# 140810_AriloTX_REV3_0_0_868MHZ_td.net
KiCad netlist of a schematic drawn in EAGLE
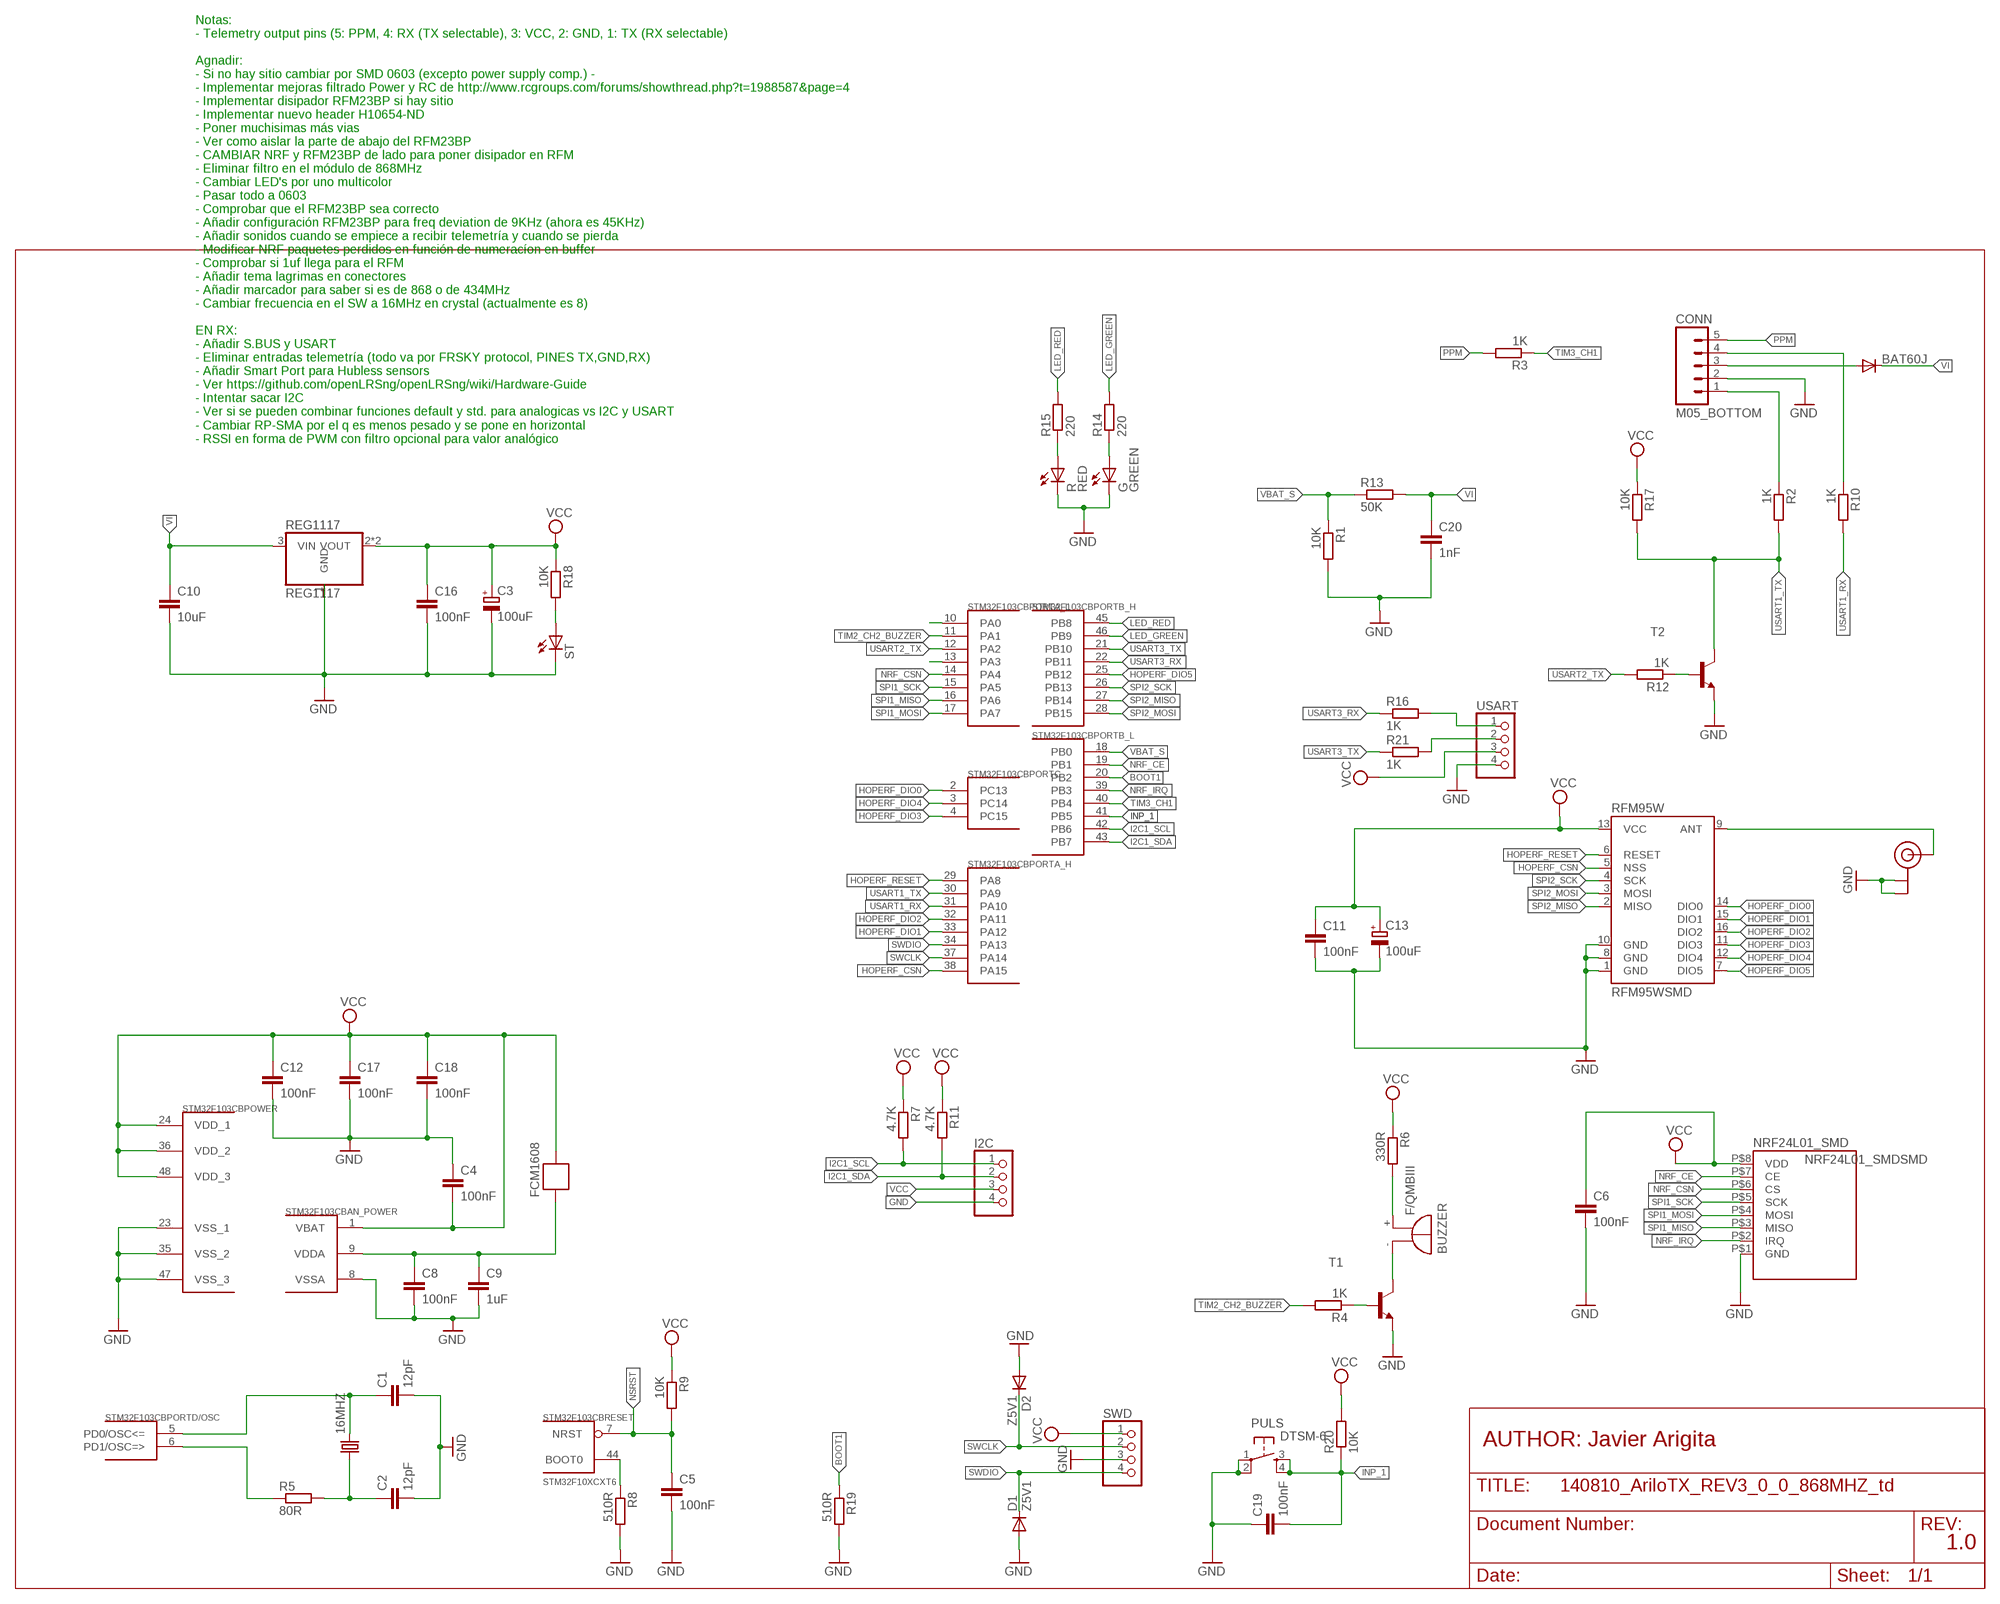
[diagram p0: schematic, sheet 1]

(export (version "E")
  (design (tool "Eeschema 10.0.6"))
  (components
    (comp (ref "16MHZ")
      (value "CRYSTAL5X3")
      (footprint "eagle-import:CRYSTAL-SMD-5X3")
      (libsource (lib "eagle-import") (part "CRYSTAL5X3"))
    )
    (comp (ref "BAT60J")
      (value "DIODE-SOD323-R")
      (footprint "eagle-import:SOD323-R")
      (libsource (lib "eagle-import") (part "DIODE-SOD323-R"))
    )
    (comp (ref "BUZZER")
      (value "F/QMBIII")
      (footprint "eagle-import:F_QMBIII")
      (libsource (lib "eagle-import") (part "F/QMBIII"))
    )
    (comp (ref "C1")
      (value "12pF")
      (footprint "eagle-import:C0603")
      (libsource (lib "eagle-import") (part "C-EUC0603"))
    )
    (comp (ref "C2")
      (value "12pF")
      (footprint "eagle-import:C0603")
      (libsource (lib "eagle-import") (part "C-EUC0603"))
    )
    (comp (ref "C3")
      (value "100uF")
      (footprint "eagle-import:SMC_B")
      (libsource (lib "eagle-import") (part "CPOL-EUSMCB"))
    )
    (comp (ref "C4")
      (value "100nF")
      (footprint "eagle-import:C0603")
      (libsource (lib "eagle-import") (part "C-EUC0603"))
    )
    (comp (ref "C5")
      (value "100nF")
      (footprint "eagle-import:C0603")
      (libsource (lib "eagle-import") (part "C-EUC0603"))
    )
    (comp (ref "C6")
      (value "100nF")
      (footprint "eagle-import:C0603")
      (libsource (lib "eagle-import") (part "C-EUC0603"))
    )
    (comp (ref "C8")
      (value "100nF")
      (footprint "eagle-import:C0603")
      (libsource (lib "eagle-import") (part "C-EUC0603"))
    )
    (comp (ref "C9")
      (value "1uF")
      (footprint "eagle-import:C0603")
      (libsource (lib "eagle-import") (part "C-EUC0603"))
    )
    (comp (ref "C10")
      (value "10uF")
      (footprint "eagle-import:C3216")
      (libsource (lib "eagle-import") (part "resistor_C-EUC3216"))
    )
    (comp (ref "C11")
      (value "100nF")
      (footprint "eagle-import:C0603")
      (libsource (lib "eagle-import") (part "C-EUC0603"))
    )
    (comp (ref "C12")
      (value "100nF")
      (footprint "eagle-import:C0603")
      (libsource (lib "eagle-import") (part "C-EUC0603"))
    )
    (comp (ref "C13")
      (value "100uF")
      (footprint "eagle-import:SMC_B")
      (libsource (lib "eagle-import") (part "CPOL-EUSMCB"))
    )
    (comp (ref "C16")
      (value "100nF")
      (footprint "eagle-import:C0603")
      (libsource (lib "eagle-import") (part "C-EUC0603"))
    )
    (comp (ref "C17")
      (value "100nF")
      (footprint "eagle-import:C0603")
      (libsource (lib "eagle-import") (part "C-EUC0603"))
    )
    (comp (ref "C18")
      (value "100nF")
      (footprint "eagle-import:C0603")
      (libsource (lib "eagle-import") (part "C-EUC0603"))
    )
    (comp (ref "C19")
      (value "100nF")
      (footprint "eagle-import:C0603")
      (libsource (lib "eagle-import") (part "C-EUC0603"))
    )
    (comp (ref "C20")
      (value "1nF")
      (footprint "eagle-import:C0603")
      (libsource (lib "eagle-import") (part "C-EUC0603"))
    )
    (comp (ref "CONN")
      (value "M05_BOTTOM")
      (footprint "eagle-import:M05_BOTTOM")
      (libsource (lib "eagle-import") (part "M05_BOTTOM"))
    )
    (comp (ref "D1")
      (value "Z5V1")
      (footprint "eagle-import:SOD323-R")
      (libsource (lib "eagle-import") (part "DIODE-SOD323-R"))
    )
    (comp (ref "D2")
      (value "Z5V1")
      (footprint "eagle-import:SOD323-R")
      (libsource (lib "eagle-import") (part "DIODE-SOD323-R"))
    )
    (comp (ref "FCM1608")
      (value "FERRITE-BEAD")
      (footprint "eagle-import:R0603")
      (libsource (lib "eagle-import") (part "FERRITE-BEAD"))
    )
    (comp (ref "G")
      (value "GREEN")
      (footprint "eagle-import:CHIP-LED0603")
      (libsource (lib "eagle-import") (part "LEDCHIP-LED0603"))
    )
    (comp (ref "I2C")
      (value "PINHD-1X4")
      (footprint "eagle-import:1X04")
      (libsource (lib "eagle-import") (part "PINHD-1X4"))
    )
    (comp (ref "NRF24L01_SMD")
      (value "NRF24L01_SMDSMD")
      (footprint "eagle-import:NRF24L01_SMD")
      (libsource (lib "eagle-import") (part "NRF24L01_SMDSMD"))
    )
    (comp (ref "PULS")
      (value "DTSM-6")
      (footprint "eagle-import:DTSM-6")
      (libsource (lib "eagle-import") (part "DTSM-6"))
    )
    (comp (ref "R")
      (value "RED")
      (footprint "eagle-import:CHIP-LED0603")
      (libsource (lib "eagle-import") (part "LEDCHIP-LED0603"))
    )
    (comp (ref "R1")
      (value "10K")
      (footprint "eagle-import:R0603")
      (libsource (lib "eagle-import") (part "R-EU_R0603"))
    )
    (comp (ref "R2")
      (value "1K")
      (footprint "eagle-import:R0603")
      (libsource (lib "eagle-import") (part "R-EU_R0603"))
    )
    (comp (ref "R3")
      (value "1K")
      (footprint "eagle-import:R0603")
      (libsource (lib "eagle-import") (part "R-EU_R0603"))
    )
    (comp (ref "R4")
      (value "1K")
      (footprint "eagle-import:R0603")
      (libsource (lib "eagle-import") (part "R-EU_R0603"))
    )
    (comp (ref "R5")
      (value "80R")
      (footprint "eagle-import:R0603")
      (libsource (lib "eagle-import") (part "R-EU_R0603"))
    )
    (comp (ref "R6")
      (value "330R")
      (footprint "eagle-import:R0603")
      (libsource (lib "eagle-import") (part "R-EU_R0603"))
    )
    (comp (ref "R7")
      (value "4.7K")
      (footprint "eagle-import:R0603")
      (libsource (lib "eagle-import") (part "R-EU_R0603"))
    )
    (comp (ref "R8")
      (value "510R")
      (footprint "eagle-import:R0603")
      (libsource (lib "eagle-import") (part "R-EU_R0603"))
    )
    (comp (ref "R9")
      (value "10K")
      (footprint "eagle-import:R0603")
      (libsource (lib "eagle-import") (part "R-EU_R0603"))
    )
    (comp (ref "R10")
      (value "1K")
      (footprint "eagle-import:R0603")
      (libsource (lib "eagle-import") (part "R-EU_R0603"))
    )
    (comp (ref "R11")
      (value "4.7K")
      (footprint "eagle-import:R0603")
      (libsource (lib "eagle-import") (part "R-EU_R0603"))
    )
    (comp (ref "R12")
      (value "1K")
      (footprint "eagle-import:R0603")
      (libsource (lib "eagle-import") (part "R-EU_R0603"))
    )
    (comp (ref "R13")
      (value "50K")
      (footprint "eagle-import:R0603")
      (libsource (lib "eagle-import") (part "R-EU_R0603"))
    )
    (comp (ref "R14")
      (value "220")
      (footprint "eagle-import:R0603")
      (libsource (lib "eagle-import") (part "R-EU_R0603"))
    )
    (comp (ref "R15")
      (value "220")
      (footprint "eagle-import:R0603")
      (libsource (lib "eagle-import") (part "R-EU_R0603"))
    )
    (comp (ref "R16")
      (value "1K")
      (footprint "eagle-import:R0603")
      (libsource (lib "eagle-import") (part "R-EU_R0603"))
    )
    (comp (ref "R17")
      (value "10K")
      (footprint "eagle-import:R0603")
      (libsource (lib "eagle-import") (part "R-EU_R0603"))
    )
    (comp (ref "R18")
      (value "10K")
      (footprint "eagle-import:R0603")
      (libsource (lib "eagle-import") (part "R-EU_R0603"))
    )
    (comp (ref "R19")
      (value "510R")
      (footprint "eagle-import:R0603")
      (libsource (lib "eagle-import") (part "R-EU_R0603"))
    )
    (comp (ref "R20")
      (value "10K")
      (footprint "eagle-import:R0603")
      (libsource (lib "eagle-import") (part "R-EU_R0603"))
    )
    (comp (ref "R21")
      (value "1K")
      (footprint "eagle-import:R0603")
      (libsource (lib "eagle-import") (part "R-EU_R0603"))
    )
    (comp (ref "REG1117")
      (value "REG1117")
      (footprint "eagle-import:SOT223")
      (libsource (lib "eagle-import") (part "REG1117"))
    )
    (comp (ref "RFM95W")
      (value "RFM95WSMD")
      (footprint "eagle-import:MISIEK_RFM95W_SMD")
      (libsource (lib "eagle-import") (part "MISIEK_RFM95WSMD"))
    )
    (comp (ref "ST")
      (value "LEDCHIP-LED0603")
      (footprint "eagle-import:CHIP-LED0603")
      (libsource (lib "eagle-import") (part "LEDCHIP-LED0603"))
    )
    (comp (ref "STM32F103CB")
      (value "STM32F10XCXT6")
      (footprint "eagle-import:TQFP48")
      (libsource (lib "eagle-import") (part "STM32F10XCXT6"))
    )
    (comp (ref "SWD")
      (value "PINHD-1X4")
      (footprint "eagle-import:1X04")
      (libsource (lib "eagle-import") (part "PINHD-1X4"))
    )
    (comp (ref "T1")
      (value "BC848-NPN-SOT23-BEC")
      (footprint "eagle-import:SOT23-BEC")
      (libsource (lib "eagle-import") (part "-NPN-SOT23-BECBC848"))
    )
    (comp (ref "T2")
      (value "BC848-NPN-SOT23-BEC")
      (footprint "eagle-import:SOT23-BEC")
      (libsource (lib "eagle-import") (part "-NPN-SOT23-BECBC848"))
    )
    (comp (ref "U.FL")
      (value "U.FL")
      (footprint "eagle-import:U.FL")
      (libsource (lib "eagle-import") (part "U.FL"))
    )
    (comp (ref "USART")
      (value "PINHD-1X4")
      (footprint "eagle-import:1X04")
      (libsource (lib "eagle-import") (part "PINHD-1X4"))
    )
  )
  (nets
    (net (code "1") (name "BOOT1") (class "Default")
      (node (ref "R19") (pin "1") (pinfunction "1_1") (pintype "passive"))
      (node (ref "STM32F103CB") (pin "20") (pinfunction "PB2_20") (pintype "bidirectional"))
    )
    (net (code "2") (name "GND") (class "Default")
      (node (ref "C1") (pin "2") (pinfunction "2_2") (pintype "passive"))
      (node (ref "C10") (pin "2") (pinfunction "2_2") (pintype "passive"))
      (node (ref "C11") (pin "2") (pinfunction "2_2") (pintype "passive"))
      (node (ref "C12") (pin "2") (pinfunction "2_2") (pintype "passive"))
      (node (ref "C13") (pin "-") (pinfunction "-_-") (pintype "passive"))
      (node (ref "C16") (pin "2") (pinfunction "2_2") (pintype "passive"))
      (node (ref "C17") (pin "2") (pinfunction "2_2") (pintype "passive"))
      (node (ref "C18") (pin "2") (pinfunction "2_2") (pintype "passive"))
      (node (ref "C19") (pin "1") (pinfunction "1_1") (pintype "passive"))
      (node (ref "C2") (pin "2") (pinfunction "2_2") (pintype "passive"))
      (node (ref "C20") (pin "2") (pinfunction "2_2") (pintype "passive"))
      (node (ref "C3") (pin "-") (pinfunction "-_-") (pintype "passive"))
      (node (ref "C4") (pin "1") (pinfunction "1_1") (pintype "passive"))
      (node (ref "C5") (pin "2") (pinfunction "2_2") (pintype "passive"))
      (node (ref "C6") (pin "2") (pinfunction "2_2") (pintype "passive"))
      (node (ref "C8") (pin "2") (pinfunction "2_2") (pintype "passive"))
      (node (ref "C9") (pin "2") (pinfunction "2_2") (pintype "passive"))
      (node (ref "CONN") (pin "2") (pinfunction "2_2") (pintype "passive"))
      (node (ref "D1") (pin "A") (pinfunction "A_A") (pintype "passive"))
      (node (ref "D2") (pin "A") (pinfunction "A_A") (pintype "passive"))
      (node (ref "G") (pin "C") (pinfunction "C_C") (pintype "passive"))
      (node (ref "I2C") (pin "4") (pinfunction "4_4") (pintype "passive"))
      (node (ref "NRF24L01_SMD") (pin "P$1") (pinfunction "GND_P$1") (pintype "power_in"))
      (node (ref "PULS") (pin "1") (pinfunction "1_1") (pintype "passive"))
      (node (ref "PULS") (pin "2") (pinfunction "2_2") (pintype "passive"))
      (node (ref "R") (pin "C") (pinfunction "C_C") (pintype "passive"))
      (node (ref "R1") (pin "2") (pinfunction "2_2") (pintype "passive"))
      (node (ref "R19") (pin "2") (pinfunction "2_2") (pintype "passive"))
      (node (ref "R8") (pin "2") (pinfunction "2_2") (pintype "passive"))
      (node (ref "REG1117") (pin "1") (pinfunction "GND_1") (pintype "power_in"))
      (node (ref "RFM95W") (pin "1") (pinfunction "GND_1") (pintype "power_in"))
      (node (ref "RFM95W") (pin "10") (pinfunction "GND_10") (pintype "power_in"))
      (node (ref "RFM95W") (pin "8") (pinfunction "GND_8") (pintype "power_in"))
      (node (ref "ST") (pin "C") (pinfunction "C_C") (pintype "passive"))
      (node (ref "STM32F103CB") (pin "23") (pinfunction "VSS_1_23") (pintype "power_in"))
      (node (ref "STM32F103CB") (pin "35") (pinfunction "VSS_2_35") (pintype "power_in"))
      (node (ref "STM32F103CB") (pin "47") (pinfunction "VSS_3_47") (pintype "power_in"))
      (node (ref "STM32F103CB") (pin "8") (pinfunction "VSSA_8") (pintype "power_in"))
      (node (ref "SWD") (pin "3") (pinfunction "3_3") (pintype "passive"))
      (node (ref "T1") (pin "E") (pinfunction "E_E") (pintype "passive"))
      (node (ref "T2") (pin "E") (pinfunction "E_E") (pintype "passive"))
      (node (ref "U.FL") (pin "P$1") (pinfunction "GND_P$1") (pintype "bidirectional"))
      (node (ref "U.FL") (pin "P$2") (pinfunction "GND_P$2") (pintype "bidirectional"))
      (node (ref "USART") (pin "4") (pinfunction "4_4") (pintype "passive"))
    )
    (net (code "3") (name "HOPERF_CSN") (class "Default")
      (node (ref "RFM95W") (pin "5") (pinfunction "NSS_5") (pintype "input"))
      (node (ref "STM32F103CB") (pin "38") (pinfunction "PA15_38") (pintype "bidirectional"))
    )
    (net (code "4") (name "HOPERF_DIO0") (class "Default")
      (node (ref "RFM95W") (pin "14") (pinfunction "DIO0_14") (pintype "input"))
      (node (ref "STM32F103CB") (pin "2") (pinfunction "PC13_2") (pintype "bidirectional"))
    )
    (net (code "5") (name "HOPERF_DIO1") (class "Default")
      (node (ref "RFM95W") (pin "15") (pinfunction "DIO1_15") (pintype "input"))
      (node (ref "STM32F103CB") (pin "33") (pinfunction "PA12_33") (pintype "bidirectional"))
    )
    (net (code "6") (name "HOPERF_DIO2") (class "Default")
      (node (ref "RFM95W") (pin "16") (pinfunction "DIO2_16") (pintype "input"))
      (node (ref "STM32F103CB") (pin "32") (pinfunction "PA11_32") (pintype "bidirectional"))
    )
    (net (code "7") (name "HOPERF_DIO3") (class "Default")
      (node (ref "RFM95W") (pin "11") (pinfunction "DIO3_11") (pintype "bidirectional"))
      (node (ref "STM32F103CB") (pin "4") (pinfunction "PC15_4") (pintype "bidirectional"))
    )
    (net (code "8") (name "HOPERF_DIO4") (class "Default")
      (node (ref "RFM95W") (pin "12") (pinfunction "DIO4_12") (pintype "bidirectional"))
      (node (ref "STM32F103CB") (pin "3") (pinfunction "PC14_3") (pintype "bidirectional"))
    )
    (net (code "9") (name "HOPERF_DIO5") (class "Default")
      (node (ref "RFM95W") (pin "7") (pinfunction "DIO5_7") (pintype "bidirectional"))
      (node (ref "STM32F103CB") (pin "25") (pinfunction "PB12_25") (pintype "bidirectional"))
    )
    (net (code "10") (name "HOPERF_RESET") (class "Default")
      (node (ref "RFM95W") (pin "6") (pinfunction "RESET_6") (pintype "output"))
      (node (ref "STM32F103CB") (pin "29") (pinfunction "PA8_29") (pintype "bidirectional"))
    )
    (net (code "11") (name "I2C1_SCL") (class "Default")
      (node (ref "I2C") (pin "1") (pinfunction "1_1") (pintype "passive"))
      (node (ref "R7") (pin "2") (pinfunction "2_2") (pintype "passive"))
      (node (ref "STM32F103CB") (pin "42") (pinfunction "PB6_42") (pintype "bidirectional"))
    )
    (net (code "12") (name "I2C1_SDA") (class "Default")
      (node (ref "I2C") (pin "2") (pinfunction "2_2") (pintype "passive"))
      (node (ref "R11") (pin "2") (pinfunction "2_2") (pintype "passive"))
      (node (ref "STM32F103CB") (pin "43") (pinfunction "PB7_43") (pintype "bidirectional"))
    )
    (net (code "13") (name "INP_1") (class "Default")
      (node (ref "C19") (pin "2") (pinfunction "2_2") (pintype "passive"))
      (node (ref "PULS") (pin "3") (pinfunction "3_3") (pintype "passive"))
      (node (ref "PULS") (pin "4") (pinfunction "4_4") (pintype "passive"))
      (node (ref "R20") (pin "1") (pinfunction "1_1") (pintype "passive"))
      (node (ref "STM32F103CB") (pin "41") (pinfunction "PB5_41") (pintype "bidirectional"))
    )
    (net (code "14") (name "LED_GREEN") (class "Default")
      (node (ref "R14") (pin "2") (pinfunction "2_2") (pintype "passive"))
      (node (ref "STM32F103CB") (pin "46") (pinfunction "PB9_46") (pintype "bidirectional"))
    )
    (net (code "15") (name "LED_RED") (class "Default")
      (node (ref "R15") (pin "2") (pinfunction "2_2") (pintype "passive"))
      (node (ref "STM32F103CB") (pin "45") (pinfunction "PB8_45") (pintype "bidirectional"))
    )
    (net (code "16") (name "NRF_CE") (class "Default")
      (node (ref "NRF24L01_SMD") (pin "P$7") (pinfunction "CE_P$7") (pintype "input"))
      (node (ref "STM32F103CB") (pin "19") (pinfunction "PB1_19") (pintype "bidirectional"))
    )
    (net (code "17") (name "NRF_CSN") (class "Default")
      (node (ref "NRF24L01_SMD") (pin "P$6") (pinfunction "CS_P$6") (pintype "input"))
      (node (ref "STM32F103CB") (pin "14") (pinfunction "PA4_14") (pintype "bidirectional"))
    )
    (net (code "18") (name "NRF_IRQ") (class "Default")
      (node (ref "NRF24L01_SMD") (pin "P$2") (pinfunction "IRQ_P$2") (pintype "output"))
      (node (ref "STM32F103CB") (pin "39") (pinfunction "PB3_39") (pintype "bidirectional"))
    )
    (net (code "19") (name "NSRST") (class "Default")
      (node (ref "C5") (pin "1") (pinfunction "1_1") (pintype "passive"))
      (node (ref "R9") (pin "2") (pinfunction "2_2") (pintype "passive"))
      (node (ref "STM32F103CB") (pin "7") (pinfunction "NRST_7") (pintype "input"))
    )
    (net (code "20") (name "Net-(16MHZ-2)") (class "Default")
      (node (ref "16MHZ") (pin "3") (pinfunction "2_3") (pintype "passive"))
      (node (ref "C1") (pin "1") (pinfunction "1_1") (pintype "passive"))
      (node (ref "STM32F103CB") (pin "5") (pinfunction "PD0/OSC<=_5") (pintype "bidirectional"))
    )
    (net (code "21") (name "Net-(16MHZ-Pad1)") (class "Default")
      (node (ref "16MHZ") (pin "1") (pinfunction "1_1") (pintype "passive"))
      (node (ref "C2") (pin "1") (pinfunction "1_1") (pintype "passive"))
      (node (ref "R5") (pin "2") (pinfunction "2_2") (pintype "passive"))
    )
    (net (code "22") (name "Net-(BAT60J-PadA)") (class "Default")
      (node (ref "BAT60J") (pin "A") (pinfunction "A_A") (pintype "passive"))
      (node (ref "CONN") (pin "3") (pinfunction "3_3") (pintype "passive"))
    )
    (net (code "23") (name "Net-(BUZZER-+)") (class "Default")
      (node (ref "BUZZER") (pin "-") (pinfunction "+_-") (pintype "passive"))
      (node (ref "T1") (pin "C") (pinfunction "C_C") (pintype "passive"))
    )
    (net (code "24") (name "Net-(BUZZER--)") (class "Default")
      (node (ref "BUZZER") (pin "+") (pinfunction "-_+") (pintype "passive"))
      (node (ref "R6") (pin "2") (pinfunction "2_2") (pintype "passive"))
    )
    (net (code "25") (name "Net-(CONN-Pad1)") (class "Default")
      (node (ref "CONN") (pin "1") (pinfunction "1_1") (pintype "passive"))
      (node (ref "R2") (pin "1") (pinfunction "1_1") (pintype "passive"))
    )
    (net (code "26") (name "Net-(CONN-Pad4)") (class "Default")
      (node (ref "CONN") (pin "4") (pinfunction "4_4") (pintype "passive"))
      (node (ref "R10") (pin "1") (pinfunction "1_1") (pintype "passive"))
    )
    (net (code "27") (name "Net-(FCM1608-P$2)") (class "Default")
      (node (ref "C8") (pin "1") (pinfunction "1_1") (pintype "passive"))
      (node (ref "C9") (pin "1") (pinfunction "1_1") (pintype "passive"))
      (node (ref "FCM1608") (pin "2") (pinfunction "P$2_2") (pintype "bidirectional"))
      (node (ref "STM32F103CB") (pin "9") (pinfunction "VDDA_9") (pintype "power_in"))
    )
    (net (code "28") (name "Net-(G-PadA)") (class "Default")
      (node (ref "G") (pin "A") (pinfunction "A_A") (pintype "passive"))
      (node (ref "R14") (pin "1") (pinfunction "1_1") (pintype "passive"))
    )
    (net (code "29") (name "Net-(R-PadA)") (class "Default")
      (node (ref "R") (pin "A") (pinfunction "A_A") (pintype "passive"))
      (node (ref "R15") (pin "1") (pinfunction "1_1") (pintype "passive"))
    )
    (net (code "30") (name "Net-(R4-Pad1)") (class "Default")
      (node (ref "R4") (pin "1") (pinfunction "1_1") (pintype "passive"))
      (node (ref "T1") (pin "B") (pinfunction "B_B") (pintype "passive"))
    )
    (net (code "31") (name "Net-(R12-Pad1)") (class "Default")
      (node (ref "R12") (pin "1") (pinfunction "1_1") (pintype "passive"))
      (node (ref "T2") (pin "B") (pinfunction "B_B") (pintype "passive"))
    )
    (net (code "32") (name "Net-(R16-Pad2)") (class "Default")
      (node (ref "R16") (pin "2") (pinfunction "2_2") (pintype "passive"))
      (node (ref "USART") (pin "1") (pinfunction "1_1") (pintype "passive"))
    )
    (net (code "33") (name "Net-(R18-Pad2)") (class "Default")
      (node (ref "R18") (pin "2") (pinfunction "2_2") (pintype "passive"))
      (node (ref "ST") (pin "A") (pinfunction "A_A") (pintype "passive"))
    )
    (net (code "34") (name "Net-(R21-Pad2)") (class "Default")
      (node (ref "R21") (pin "2") (pinfunction "2_2") (pintype "passive"))
      (node (ref "USART") (pin "2") (pinfunction "2_2") (pintype "passive"))
    )
    (net (code "35") (name "Net-(RFM95W-ANT)") (class "Default")
      (node (ref "RFM95W") (pin "9") (pinfunction "ANT_9") (pintype "bidirectional"))
      (node (ref "U.FL") (pin "P$3") (pinfunction "SIGNAL_P$3") (pintype "bidirectional"))
    )
    (net (code "36") (name "Net-(STM32F103CBG-PD1{slash}OSC=>)") (class "Default")
      (node (ref "R5") (pin "1") (pinfunction "1_1") (pintype "passive"))
      (node (ref "STM32F103CB") (pin "6") (pinfunction "PD1/OSC=>_6") (pintype "bidirectional"))
    )
    (net (code "37") (name "Net-(STM32F103CBI-BOOT0)") (class "Default")
      (node (ref "R8") (pin "1") (pinfunction "1_1") (pintype "passive"))
      (node (ref "STM32F103CB") (pin "44") (pinfunction "BOOT0_44") (pintype "input"))
    )
    (net (code "38") (name "PPM") (class "Default")
      (node (ref "CONN") (pin "5") (pinfunction "5_5") (pintype "passive"))
      (node (ref "R3") (pin "2") (pinfunction "2_2") (pintype "passive"))
    )
    (net (code "39") (name "SPI1_MISO") (class "Default")
      (node (ref "NRF24L01_SMD") (pin "P$3") (pinfunction "MISO_P$3") (pintype "output"))
      (node (ref "STM32F103CB") (pin "16") (pinfunction "PA6_16") (pintype "bidirectional"))
    )
    (net (code "40") (name "SPI1_MOSI") (class "Default")
      (node (ref "NRF24L01_SMD") (pin "P$4") (pinfunction "MOSI_P$4") (pintype "input"))
      (node (ref "STM32F103CB") (pin "17") (pinfunction "PA7_17") (pintype "bidirectional"))
    )
    (net (code "41") (name "SPI1_SCK") (class "Default")
      (node (ref "NRF24L01_SMD") (pin "P$5") (pinfunction "SCK_P$5") (pintype "input"))
      (node (ref "STM32F103CB") (pin "15") (pinfunction "PA5_15") (pintype "bidirectional"))
    )
    (net (code "42") (name "SPI2_MISO") (class "Default")
      (node (ref "RFM95W") (pin "2") (pinfunction "MISO_2") (pintype "output"))
      (node (ref "STM32F103CB") (pin "27") (pinfunction "PB14_27") (pintype "bidirectional"))
    )
    (net (code "43") (name "SPI2_MOSI") (class "Default")
      (node (ref "RFM95W") (pin "3") (pinfunction "MOSI_3") (pintype "input"))
      (node (ref "STM32F103CB") (pin "28") (pinfunction "PB15_28") (pintype "bidirectional"))
    )
    (net (code "44") (name "SPI2_SCK") (class "Default")
      (node (ref "RFM95W") (pin "4") (pinfunction "SCK_4") (pintype "input"))
      (node (ref "STM32F103CB") (pin "26") (pinfunction "PB13_26") (pintype "bidirectional"))
    )
    (net (code "45") (name "SWCLK") (class "Default")
      (node (ref "D2") (pin "C") (pinfunction "C_C") (pintype "passive"))
      (node (ref "STM32F103CB") (pin "37") (pinfunction "PA14_37") (pintype "bidirectional"))
      (node (ref "SWD") (pin "2") (pinfunction "2_2") (pintype "passive"))
    )
    (net (code "46") (name "SWDIO") (class "Default")
      (node (ref "D1") (pin "C") (pinfunction "C_C") (pintype "passive"))
      (node (ref "STM32F103CB") (pin "34") (pinfunction "PA13_34") (pintype "bidirectional"))
      (node (ref "SWD") (pin "4") (pinfunction "4_4") (pintype "passive"))
    )
    (net (code "47") (name "TIM2_CH2_BUZZER") (class "Default")
      (node (ref "R4") (pin "2") (pinfunction "2_2") (pintype "passive"))
      (node (ref "STM32F103CB") (pin "11") (pinfunction "PA1_11") (pintype "bidirectional"))
    )
    (net (code "48") (name "TIM3_CH1") (class "Default")
      (node (ref "R3") (pin "1") (pinfunction "1_1") (pintype "passive"))
      (node (ref "STM32F103CB") (pin "40") (pinfunction "PB4_40") (pintype "bidirectional"))
    )
    (net (code "49") (name "USART1_RX") (class "Default")
      (node (ref "R10") (pin "2") (pinfunction "2_2") (pintype "passive"))
      (node (ref "STM32F103CB") (pin "31") (pinfunction "PA10_31") (pintype "bidirectional"))
    )
    (net (code "50") (name "USART1_TX") (class "Default")
      (node (ref "R17") (pin "2") (pinfunction "2_2") (pintype "passive"))
      (node (ref "R2") (pin "2") (pinfunction "2_2") (pintype "passive"))
      (node (ref "STM32F103CB") (pin "30") (pinfunction "PA9_30") (pintype "bidirectional"))
      (node (ref "T2") (pin "C") (pinfunction "C_C") (pintype "passive"))
    )
    (net (code "51") (name "USART2_TX") (class "Default")
      (node (ref "R12") (pin "2") (pinfunction "2_2") (pintype "passive"))
      (node (ref "STM32F103CB") (pin "12") (pinfunction "PA2_12") (pintype "bidirectional"))
    )
    (net (code "52") (name "USART3_RX") (class "Default")
      (node (ref "R16") (pin "1") (pinfunction "1_1") (pintype "passive"))
      (node (ref "STM32F103CB") (pin "22") (pinfunction "PB11_22") (pintype "bidirectional"))
    )
    (net (code "53") (name "USART3_TX") (class "Default")
      (node (ref "R21") (pin "1") (pinfunction "1_1") (pintype "passive"))
      (node (ref "STM32F103CB") (pin "21") (pinfunction "PB10_21") (pintype "bidirectional"))
    )
    (net (code "54") (name "VBAT_S") (class "Default")
      (node (ref "R1") (pin "1") (pinfunction "1_1") (pintype "passive"))
      (node (ref "R13") (pin "1") (pinfunction "1_1") (pintype "passive"))
      (node (ref "STM32F103CB") (pin "18") (pinfunction "PB0_18") (pintype "bidirectional"))
    )
    (net (code "55") (name "VCC") (class "Default")
      (node (ref "C11") (pin "1") (pinfunction "1_1") (pintype "passive"))
      (node (ref "C12") (pin "1") (pinfunction "1_1") (pintype "passive"))
      (node (ref "C13") (pin "+") (pinfunction "+_+") (pintype "passive"))
      (node (ref "C16") (pin "1") (pinfunction "1_1") (pintype "passive"))
      (node (ref "C17") (pin "1") (pinfunction "1_1") (pintype "passive"))
      (node (ref "C18") (pin "1") (pinfunction "1_1") (pintype "passive"))
      (node (ref "C3") (pin "+") (pinfunction "+_+") (pintype "passive"))
      (node (ref "C4") (pin "2") (pinfunction "2_2") (pintype "passive"))
      (node (ref "C6") (pin "1") (pinfunction "1_1") (pintype "passive"))
      (node (ref "FCM1608") (pin "1") (pinfunction "P$1_1") (pintype "bidirectional"))
      (node (ref "I2C") (pin "3") (pinfunction "3_3") (pintype "passive"))
      (node (ref "NRF24L01_SMD") (pin "P$8") (pinfunction "VDD_P$8") (pintype "bidirectional"))
      (node (ref "R11") (pin "1") (pinfunction "1_1") (pintype "passive"))
      (node (ref "R17") (pin "1") (pinfunction "1_1") (pintype "passive"))
      (node (ref "R18") (pin "1") (pinfunction "1_1") (pintype "passive"))
      (node (ref "R20") (pin "2") (pinfunction "2_2") (pintype "passive"))
      (node (ref "R6") (pin "1") (pinfunction "1_1") (pintype "passive"))
      (node (ref "R7") (pin "1") (pinfunction "1_1") (pintype "passive"))
      (node (ref "R9") (pin "1") (pinfunction "1_1") (pintype "passive"))
      (node (ref "REG1117") (pin "2") (pinfunction "VOUT_2") (pintype "power_in"))
      (node (ref "REG1117") (pin "4") (pinfunction "VOUT_4") (pintype "power_in"))
      (node (ref "RFM95W") (pin "13") (pinfunction "VCC_13") (pintype "bidirectional"))
      (node (ref "STM32F103CB") (pin "1") (pinfunction "VBAT_1") (pintype "power_in"))
      (node (ref "STM32F103CB") (pin "24") (pinfunction "VDD_1_24") (pintype "power_in"))
      (node (ref "STM32F103CB") (pin "36") (pinfunction "VDD_2_36") (pintype "power_in"))
      (node (ref "STM32F103CB") (pin "48") (pinfunction "VDD_3_48") (pintype "power_in"))
      (node (ref "SWD") (pin "1") (pinfunction "1_1") (pintype "passive"))
      (node (ref "USART") (pin "3") (pinfunction "3_3") (pintype "passive"))
    )
    (net (code "56") (name "VI") (class "Default")
      (node (ref "BAT60J") (pin "C") (pinfunction "C_C") (pintype "passive"))
      (node (ref "C10") (pin "1") (pinfunction "1_1") (pintype "passive"))
      (node (ref "C20") (pin "1") (pinfunction "1_1") (pintype "passive"))
      (node (ref "R13") (pin "2") (pinfunction "2_2") (pintype "passive"))
      (node (ref "REG1117") (pin "3") (pinfunction "VIN_3") (pintype "input"))
    )
    (net (code "57") (name "unconnected-(STM32F103CBC-PA0-Pad10)") (class "Default")
      (node (ref "STM32F103CB") (pin "10") (pinfunction "PA0_10") (pintype "bidirectional"))
    )
    (net (code "58") (name "unconnected-(STM32F103CBC-PA3-Pad13)") (class "Default")
      (node (ref "STM32F103CB") (pin "13") (pinfunction "PA3_13") (pintype "bidirectional"))
    )
  )
)
